# control.net
KiCad netlist of a schematic drawn in EAGLE
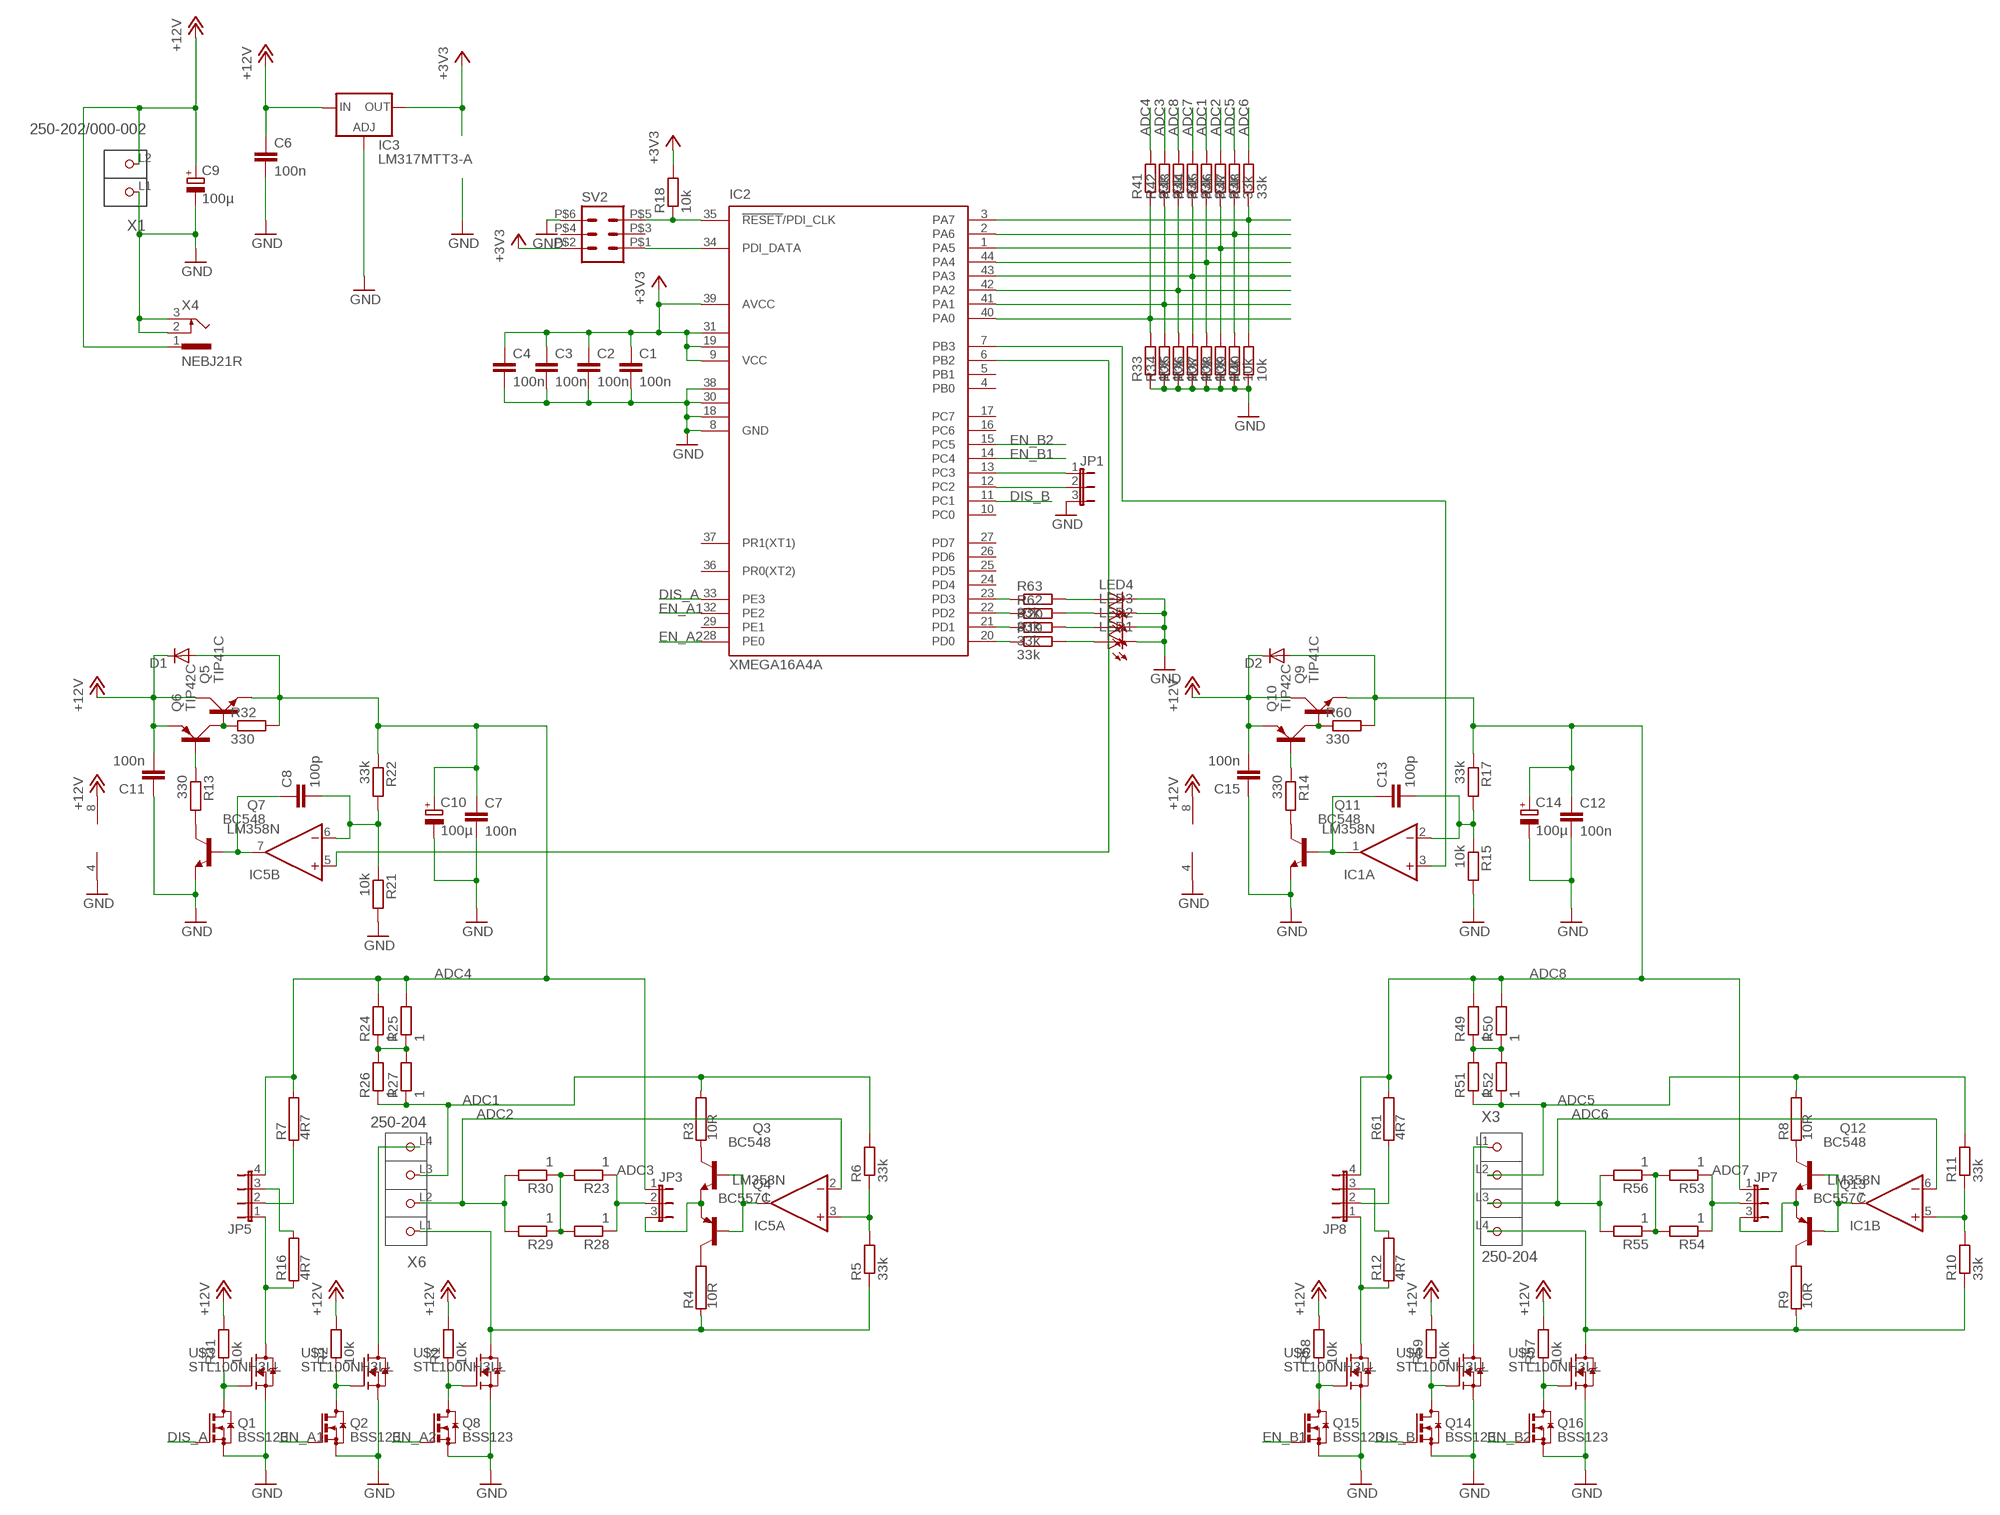
[diagram p0: schematic, sheet 1]

(export (version "E")
  (design (tool "Eeschema 10.0.6"))
  (components
    (comp (ref "C1")
      (value "100n")
      (footprint "eagle-import:C0805K")
      (libsource (lib "eagle-import") (part "C-EUC0805K"))
    )
    (comp (ref "C2")
      (value "100n")
      (footprint "eagle-import:C0805K")
      (libsource (lib "eagle-import") (part "C-EUC0805K"))
    )
    (comp (ref "C3")
      (value "100n")
      (footprint "eagle-import:C0805K")
      (libsource (lib "eagle-import") (part "C-EUC0805K"))
    )
    (comp (ref "C4")
      (value "100n")
      (footprint "eagle-import:C0805K")
      (libsource (lib "eagle-import") (part "C-EUC0805K"))
    )
    (comp (ref "C6")
      (value "100n")
      (footprint "eagle-import:C0805K")
      (libsource (lib "eagle-import") (part "C-EUC0805K"))
    )
    (comp (ref "C7")
      (value "100n")
      (footprint "eagle-import:C0805K")
      (libsource (lib "eagle-import") (part "C-EUC0805K"))
    )
    (comp (ref "C8")
      (value "100p")
      (footprint "eagle-import:C0805K")
      (libsource (lib "eagle-import") (part "C-EUC0805K"))
    )
    (comp (ref "C9")
      (value "100µ")
      (footprint "eagle-import:E2,5-7")
      (libsource (lib "eagle-import") (part "CPOL-EUE2.5-7"))
    )
    (comp (ref "C10")
      (value "100µ")
      (footprint "eagle-import:E2,5-7")
      (libsource (lib "eagle-import") (part "CPOL-EUE2.5-7"))
    )
    (comp (ref "C11")
      (value "100n")
      (footprint "eagle-import:C0805")
      (libsource (lib "eagle-import") (part "C-EUC0805"))
    )
    (comp (ref "C12")
      (value "100n")
      (footprint "eagle-import:C0805K")
      (libsource (lib "eagle-import") (part "C-EUC0805K"))
    )
    (comp (ref "C13")
      (value "100p")
      (footprint "eagle-import:C0805K")
      (libsource (lib "eagle-import") (part "C-EUC0805K"))
    )
    (comp (ref "C14")
      (value "100µ")
      (footprint "eagle-import:E2,5-7")
      (libsource (lib "eagle-import") (part "CPOL-EUE2.5-7"))
    )
    (comp (ref "C15")
      (value "100n")
      (footprint "eagle-import:C0805")
      (libsource (lib "eagle-import") (part "C-EUC0805"))
    )
    (comp (ref "D1")
      (value "DIODE-DO41-7.6")
      (footprint "eagle-import:DO41-7.6")
      (libsource (lib "eagle-import") (part "DIODE-DO41-7.6"))
    )
    (comp (ref "D2")
      (value "DIODE-DO41-7.6")
      (footprint "eagle-import:DO41-7.6")
      (libsource (lib "eagle-import") (part "DIODE-DO41-7.6"))
    )
    (comp (ref "IC1")
      (value "LM358N")
      (footprint "eagle-import:DIL08")
      (libsource (lib "eagle-import") (part "LM358N"))
    )
    (comp (ref "IC2")
      (value "XMEGA16A4A")
      (footprint "eagle-import:TQFP44")
      (libsource (lib "eagle-import") (part "XMEGA16A4A"))
    )
    (comp (ref "IC3")
      (value "LM317MTT3-A")
      (footprint "eagle-import:SOT223")
      (libsource (lib "eagle-import") (part "LM317?MTT3-A"))
    )
    (comp (ref "IC5")
      (value "LM358N")
      (footprint "eagle-import:DIL08")
      (libsource (lib "eagle-import") (part "LM358N"))
    )
    (comp (ref "JP1")
      (value "JP2E")
      (footprint "eagle-import:JP2")
      (libsource (lib "eagle-import") (part "JP2E"))
    )
    (comp (ref "JP3")
      (value "JP2E")
      (footprint "eagle-import:JP2")
      (libsource (lib "eagle-import") (part "JP2E"))
    )
    (comp (ref "JP5")
      (value "JP4E")
      (footprint "eagle-import:JP4")
      (libsource (lib "eagle-import") (part "JP4E"))
    )
    (comp (ref "JP7")
      (value "JP2E")
      (footprint "eagle-import:JP2")
      (libsource (lib "eagle-import") (part "JP2E"))
    )
    (comp (ref "JP8")
      (value "JP4E")
      (footprint "eagle-import:JP4")
      (libsource (lib "eagle-import") (part "JP4E"))
    )
    (comp (ref "LED1")
      (value "LEDCHIPLED_0805")
      (footprint "eagle-import:CHIPLED_0805")
      (libsource (lib "eagle-import") (part "LEDCHIPLED_0805"))
    )
    (comp (ref "LED2")
      (value "LEDCHIPLED_0805")
      (footprint "eagle-import:CHIPLED_0805")
      (libsource (lib "eagle-import") (part "LEDCHIPLED_0805"))
    )
    (comp (ref "LED3")
      (value "LEDCHIPLED_0805")
      (footprint "eagle-import:CHIPLED_0805")
      (libsource (lib "eagle-import") (part "LEDCHIPLED_0805"))
    )
    (comp (ref "LED4")
      (value "LEDCHIPLED_0805")
      (footprint "eagle-import:CHIPLED_0805")
      (libsource (lib "eagle-import") (part "LEDCHIPLED_0805"))
    )
    (comp (ref "Q1")
      (value "BSS123")
      (footprint "eagle-import:SOT23")
      (libsource (lib "eagle-import") (part "BSS123"))
    )
    (comp (ref "Q2")
      (value "BSS123")
      (footprint "eagle-import:SOT23")
      (libsource (lib "eagle-import") (part "BSS123"))
    )
    (comp (ref "Q3")
      (value "BC548")
      (footprint "eagle-import:TO92-EBC")
      (libsource (lib "eagle-import") (part "BC548"))
    )
    (comp (ref "Q4")
      (value "BC557C")
      (footprint "eagle-import:TO92-EBC")
      (libsource (lib "eagle-import") (part "BC557C"))
    )
    (comp (ref "Q5")
      (value "TIP41C")
      (footprint "eagle-import:TO220AV")
      (libsource (lib "eagle-import") (part "TIP41C"))
    )
    (comp (ref "Q6")
      (value "TIP42C")
      (footprint "eagle-import:TO220AV")
      (libsource (lib "eagle-import") (part "TIP42C"))
    )
    (comp (ref "Q7")
      (value "BC548")
      (footprint "eagle-import:TO92-EBC")
      (libsource (lib "eagle-import") (part "BC548"))
    )
    (comp (ref "Q8")
      (value "BSS123")
      (footprint "eagle-import:SOT23")
      (libsource (lib "eagle-import") (part "BSS123"))
    )
    (comp (ref "Q9")
      (value "TIP41C")
      (footprint "eagle-import:TO220AV")
      (libsource (lib "eagle-import") (part "TIP41C"))
    )
    (comp (ref "Q10")
      (value "TIP42C")
      (footprint "eagle-import:TO220AV")
      (libsource (lib "eagle-import") (part "TIP42C"))
    )
    (comp (ref "Q11")
      (value "BC548")
      (footprint "eagle-import:TO92-EBC")
      (libsource (lib "eagle-import") (part "BC548"))
    )
    (comp (ref "Q12")
      (value "BC548")
      (footprint "eagle-import:TO92-EBC")
      (libsource (lib "eagle-import") (part "BC548"))
    )
    (comp (ref "Q13")
      (value "BC557C")
      (footprint "eagle-import:TO92-EBC")
      (libsource (lib "eagle-import") (part "BC557C"))
    )
    (comp (ref "Q14")
      (value "BSS123")
      (footprint "eagle-import:SOT23")
      (libsource (lib "eagle-import") (part "BSS123"))
    )
    (comp (ref "Q15")
      (value "BSS123")
      (footprint "eagle-import:SOT23")
      (libsource (lib "eagle-import") (part "BSS123"))
    )
    (comp (ref "Q16")
      (value "BSS123")
      (footprint "eagle-import:SOT23")
      (libsource (lib "eagle-import") (part "BSS123"))
    )
    (comp (ref "R1")
      (value "10k")
      (footprint "eagle-import:M0805")
      (libsource (lib "eagle-import") (part "R-EU_M0805"))
    )
    (comp (ref "R2")
      (value "10k")
      (footprint "eagle-import:M0805")
      (libsource (lib "eagle-import") (part "R-EU_M0805"))
    )
    (comp (ref "R3")
      (value "10R")
      (footprint "eagle-import:HPS58")
      (libsource (lib "eagle-import") (part "RHPS58"))
    )
    (comp (ref "R4")
      (value "10R")
      (footprint "eagle-import:HPS58")
      (libsource (lib "eagle-import") (part "RHPS58"))
    )
    (comp (ref "R5")
      (value "33k")
      (footprint "eagle-import:M0805")
      (libsource (lib "eagle-import") (part "R-EU_M0805"))
    )
    (comp (ref "R6")
      (value "33k")
      (footprint "eagle-import:M0805")
      (libsource (lib "eagle-import") (part "R-EU_M0805"))
    )
    (comp (ref "R7")
      (value "4R7")
      (footprint "eagle-import:KH208R-8")
      (libsource (lib "eagle-import") (part "RKH208-8R"))
    )
    (comp (ref "R8")
      (value "10R")
      (footprint "eagle-import:HPS58")
      (libsource (lib "eagle-import") (part "RHPS58"))
    )
    (comp (ref "R9")
      (value "10R")
      (footprint "eagle-import:HPS58")
      (libsource (lib "eagle-import") (part "RHPS58"))
    )
    (comp (ref "R10")
      (value "33k")
      (footprint "eagle-import:M0805")
      (libsource (lib "eagle-import") (part "R-EU_M0805"))
    )
    (comp (ref "R11")
      (value "33k")
      (footprint "eagle-import:M0805")
      (libsource (lib "eagle-import") (part "R-EU_M0805"))
    )
    (comp (ref "R12")
      (value "4R7")
      (footprint "eagle-import:KH208R-8")
      (libsource (lib "eagle-import") (part "RKH208-8R"))
    )
    (comp (ref "R13")
      (value "330")
      (footprint "eagle-import:M0805")
      (libsource (lib "eagle-import") (part "R-EU_M0805"))
    )
    (comp (ref "R14")
      (value "330")
      (footprint "eagle-import:M0805")
      (libsource (lib "eagle-import") (part "R-EU_M0805"))
    )
    (comp (ref "R15")
      (value "10k")
      (footprint "eagle-import:M0805")
      (libsource (lib "eagle-import") (part "R-EU_M0805"))
    )
    (comp (ref "R16")
      (value "4R7")
      (footprint "eagle-import:KH208R-8")
      (libsource (lib "eagle-import") (part "RKH208-8R"))
    )
    (comp (ref "R17")
      (value "33k")
      (footprint "eagle-import:M0805")
      (libsource (lib "eagle-import") (part "R-EU_M0805"))
    )
    (comp (ref "R18")
      (value "10k")
      (footprint "eagle-import:M0805")
      (libsource (lib "eagle-import") (part "R-EU_M0805"))
    )
    (comp (ref "R19")
      (value "33k")
      (footprint "eagle-import:M0805")
      (libsource (lib "eagle-import") (part "R-EU_M0805"))
    )
    (comp (ref "R20")
      (value "33k")
      (footprint "eagle-import:M0805")
      (libsource (lib "eagle-import") (part "R-EU_M0805"))
    )
    (comp (ref "R21")
      (value "10k")
      (footprint "eagle-import:M0805")
      (libsource (lib "eagle-import") (part "R-EU_M0805"))
    )
    (comp (ref "R22")
      (value "33k")
      (footprint "eagle-import:M0805")
      (libsource (lib "eagle-import") (part "R-EU_M0805"))
    )
    (comp (ref "R23")
      (value "1")
      (footprint "eagle-import:0207_2V")
      (libsource (lib "eagle-import") (part "R-EU_0207/2V"))
    )
    (comp (ref "R24")
      (value "1")
      (footprint "eagle-import:0207_2V")
      (libsource (lib "eagle-import") (part "R-EU_0207/2V"))
    )
    (comp (ref "R25")
      (value "1")
      (footprint "eagle-import:0207_2V")
      (libsource (lib "eagle-import") (part "R-EU_0207/2V"))
    )
    (comp (ref "R26")
      (value "1")
      (footprint "eagle-import:0207_2V")
      (libsource (lib "eagle-import") (part "R-EU_0207/2V"))
    )
    (comp (ref "R27")
      (value "1")
      (footprint "eagle-import:0207_2V")
      (libsource (lib "eagle-import") (part "R-EU_0207/2V"))
    )
    (comp (ref "R28")
      (value "1")
      (footprint "eagle-import:0207_2V")
      (libsource (lib "eagle-import") (part "R-EU_0207/2V"))
    )
    (comp (ref "R29")
      (value "1")
      (footprint "eagle-import:0207_2V")
      (libsource (lib "eagle-import") (part "R-EU_0207/2V"))
    )
    (comp (ref "R30")
      (value "1")
      (footprint "eagle-import:0207_2V")
      (libsource (lib "eagle-import") (part "R-EU_0207/2V"))
    )
    (comp (ref "R31")
      (value "10k")
      (footprint "eagle-import:M0805")
      (libsource (lib "eagle-import") (part "R-EU_M0805"))
    )
    (comp (ref "R32")
      (value "330")
      (footprint "eagle-import:M0805")
      (libsource (lib "eagle-import") (part "R-EU_M0805"))
    )
    (comp (ref "R33")
      (value "10k")
      (footprint "eagle-import:M0805")
      (libsource (lib "eagle-import") (part "R-EU_M0805"))
    )
    (comp (ref "R34")
      (value "10k")
      (footprint "eagle-import:M0805")
      (libsource (lib "eagle-import") (part "R-EU_M0805"))
    )
    (comp (ref "R35")
      (value "10k")
      (footprint "eagle-import:M0805")
      (libsource (lib "eagle-import") (part "R-EU_M0805"))
    )
    (comp (ref "R36")
      (value "10k")
      (footprint "eagle-import:M0805")
      (libsource (lib "eagle-import") (part "R-EU_M0805"))
    )
    (comp (ref "R37")
      (value "10k")
      (footprint "eagle-import:M0805")
      (libsource (lib "eagle-import") (part "R-EU_M0805"))
    )
    (comp (ref "R38")
      (value "10k")
      (footprint "eagle-import:M0805")
      (libsource (lib "eagle-import") (part "R-EU_M0805"))
    )
    (comp (ref "R39")
      (value "10k")
      (footprint "eagle-import:M0805")
      (libsource (lib "eagle-import") (part "R-EU_M0805"))
    )
    (comp (ref "R40")
      (value "10k")
      (footprint "eagle-import:M0805")
      (libsource (lib "eagle-import") (part "R-EU_M0805"))
    )
    (comp (ref "R41")
      (value "33k")
      (footprint "eagle-import:M0805")
      (libsource (lib "eagle-import") (part "R-EU_M0805"))
    )
    (comp (ref "R42")
      (value "33k")
      (footprint "eagle-import:M0805")
      (libsource (lib "eagle-import") (part "R-EU_M0805"))
    )
    (comp (ref "R43")
      (value "33k")
      (footprint "eagle-import:M0805")
      (libsource (lib "eagle-import") (part "R-EU_M0805"))
    )
    (comp (ref "R44")
      (value "33k")
      (footprint "eagle-import:M0805")
      (libsource (lib "eagle-import") (part "R-EU_M0805"))
    )
    (comp (ref "R45")
      (value "33k")
      (footprint "eagle-import:M0805")
      (libsource (lib "eagle-import") (part "R-EU_M0805"))
    )
    (comp (ref "R46")
      (value "33k")
      (footprint "eagle-import:M0805")
      (libsource (lib "eagle-import") (part "R-EU_M0805"))
    )
    (comp (ref "R47")
      (value "33k")
      (footprint "eagle-import:M0805")
      (libsource (lib "eagle-import") (part "R-EU_M0805"))
    )
    (comp (ref "R48")
      (value "33k")
      (footprint "eagle-import:M0805")
      (libsource (lib "eagle-import") (part "R-EU_M0805"))
    )
    (comp (ref "R49")
      (value "1")
      (footprint "eagle-import:0207_2V")
      (libsource (lib "eagle-import") (part "R-EU_0207/2V"))
    )
    (comp (ref "R50")
      (value "1")
      (footprint "eagle-import:0207_2V")
      (libsource (lib "eagle-import") (part "R-EU_0207/2V"))
    )
    (comp (ref "R51")
      (value "1")
      (footprint "eagle-import:0207_2V")
      (libsource (lib "eagle-import") (part "R-EU_0207/2V"))
    )
    (comp (ref "R52")
      (value "1")
      (footprint "eagle-import:0207_2V")
      (libsource (lib "eagle-import") (part "R-EU_0207/2V"))
    )
    (comp (ref "R53")
      (value "1")
      (footprint "eagle-import:0207_2V")
      (libsource (lib "eagle-import") (part "R-EU_0207/2V"))
    )
    (comp (ref "R54")
      (value "1")
      (footprint "eagle-import:0207_2V")
      (libsource (lib "eagle-import") (part "R-EU_0207/2V"))
    )
    (comp (ref "R55")
      (value "1")
      (footprint "eagle-import:0207_2V")
      (libsource (lib "eagle-import") (part "R-EU_0207/2V"))
    )
    (comp (ref "R56")
      (value "1")
      (footprint "eagle-import:0207_2V")
      (libsource (lib "eagle-import") (part "R-EU_0207/2V"))
    )
    (comp (ref "R57")
      (value "10k")
      (footprint "eagle-import:M0805")
      (libsource (lib "eagle-import") (part "R-EU_M0805"))
    )
    (comp (ref "R58")
      (value "10k")
      (footprint "eagle-import:M0805")
      (libsource (lib "eagle-import") (part "R-EU_M0805"))
    )
    (comp (ref "R59")
      (value "10k")
      (footprint "eagle-import:M0805")
      (libsource (lib "eagle-import") (part "R-EU_M0805"))
    )
    (comp (ref "R60")
      (value "330")
      (footprint "eagle-import:M0805")
      (libsource (lib "eagle-import") (part "R-EU_M0805"))
    )
    (comp (ref "R61")
      (value "4R7")
      (footprint "eagle-import:KH208R-8")
      (libsource (lib "eagle-import") (part "RKH208-8R"))
    )
    (comp (ref "R62")
      (value "33k")
      (footprint "eagle-import:M0805")
      (libsource (lib "eagle-import") (part "R-EU_M0805"))
    )
    (comp (ref "R63")
      (value "33k")
      (footprint "eagle-import:M0805")
      (libsource (lib "eagle-import") (part "R-EU_M0805"))
    )
    (comp (ref "SV2")
      (value "ML66S")
      (footprint "eagle-import:ML6S")
      (libsource (lib "eagle-import") (part "ML66S"))
    )
    (comp (ref "U$1")
      (value "STL100NH3LL")
      (footprint "eagle-import:PG-TDSON-8")
      (libsource (lib "eagle-import") (part "STL100NH3LL"))
    )
    (comp (ref "U$2")
      (value "STL100NH3LL")
      (footprint "eagle-import:PG-TDSON-8")
      (libsource (lib "eagle-import") (part "STL100NH3LL"))
    )
    (comp (ref "U$3")
      (value "STL100NH3LL")
      (footprint "eagle-import:PG-TDSON-8")
      (libsource (lib "eagle-import") (part "STL100NH3LL"))
    )
    (comp (ref "U$4")
      (value "STL100NH3LL")
      (footprint "eagle-import:PG-TDSON-8")
      (libsource (lib "eagle-import") (part "STL100NH3LL"))
    )
    (comp (ref "U$5")
      (value "STL100NH3LL")
      (footprint "eagle-import:PG-TDSON-8")
      (libsource (lib "eagle-import") (part "STL100NH3LL"))
    )
    (comp (ref "U$6")
      (value "STL100NH3LL")
      (footprint "eagle-import:PG-TDSON-8")
      (libsource (lib "eagle-import") (part "STL100NH3LL"))
    )
    (comp (ref "X1")
      (value "250-202/000-002")
      (footprint "eagle-import:P-250-202")
      (libsource (lib "eagle-import") (part "250-202/000-002"))
    )
    (comp (ref "X3")
      (value "250-204")
      (footprint "eagle-import:P-250-204")
      (libsource (lib "eagle-import") (part "250-204"))
    )
    (comp (ref "X4")
      (value "NEBJ21R")
      (footprint "eagle-import:NEBJ21R")
      (fields (field (name "MPN") "NEB/J 21 R"))
      (libsource (lib "eagle-import") (part "NEBJ21R"))
    )
    (comp (ref "X6")
      (value "250-204")
      (footprint "eagle-import:P-250-204")
      (libsource (lib "eagle-import") (part "250-204"))
    )
  )
  (nets
    (net (code "1") (name "+3V3") (class "Default")
      (node (ref "C1") (pin "1") (pinfunction "1_1") (pintype "passive"))
      (node (ref "C2") (pin "1") (pinfunction "1_1") (pintype "passive"))
      (node (ref "C3") (pin "1") (pinfunction "1_1") (pintype "passive"))
      (node (ref "C4") (pin "1") (pinfunction "1_1") (pintype "passive"))
      (node (ref "IC2") (pin "19") (pinfunction "VCC1_19") (pintype "power_in"))
      (node (ref "IC2") (pin "31") (pinfunction "VCC2_31") (pintype "power_in"))
      (node (ref "IC2") (pin "39") (pinfunction "AVCC_39") (pintype "power_in"))
      (node (ref "IC2") (pin "9") (pinfunction "VCC_9") (pintype "power_in"))
      (node (ref "IC3") (pin "2") (pinfunction "OUT_2") (pintype "passive"))
      (node (ref "R18") (pin "2") (pinfunction "2_2") (pintype "passive"))
      (node (ref "SV2") (pin "P$2") (pinfunction "2_P$2") (pintype "passive"))
    )
    (net (code "2") (name "+12V") (class "Default")
      (node (ref "C11") (pin "2") (pinfunction "2_2") (pintype "passive"))
      (node (ref "C15") (pin "2") (pinfunction "2_2") (pintype "passive"))
      (node (ref "C6") (pin "1") (pinfunction "1_1") (pintype "passive"))
      (node (ref "C9") (pin "+") (pinfunction "+_+") (pintype "passive"))
      (node (ref "D1") (pin "C") (pinfunction "C_C") (pintype "passive"))
      (node (ref "D2") (pin "C") (pinfunction "C_C") (pintype "passive"))
      (node (ref "IC1") (pin "8") (pinfunction "V+_8") (pintype "power_in"))
      (node (ref "IC3") (pin "3") (pinfunction "IN_3") (pintype "input"))
      (node (ref "IC5") (pin "8") (pinfunction "V+_8") (pintype "power_in"))
      (node (ref "Q10") (pin "E") (pinfunction "E_E") (pintype "passive"))
      (node (ref "Q5") (pin "C") (pinfunction "C_C") (pintype "passive"))
      (node (ref "Q6") (pin "E") (pinfunction "E_E") (pintype "passive"))
      (node (ref "Q9") (pin "C") (pinfunction "C_C") (pintype "passive"))
      (node (ref "R1") (pin "2") (pinfunction "2_2") (pintype "passive"))
      (node (ref "R2") (pin "2") (pinfunction "2_2") (pintype "passive"))
      (node (ref "R31") (pin "2") (pinfunction "2_2") (pintype "passive"))
      (node (ref "R57") (pin "2") (pinfunction "2_2") (pintype "passive"))
      (node (ref "R58") (pin "2") (pinfunction "2_2") (pintype "passive"))
      (node (ref "R59") (pin "2") (pinfunction "2_2") (pintype "passive"))
      (node (ref "X1") (pin "L2") (pinfunction "P2_L2") (pintype "bidirectional"))
      (node (ref "X4") (pin "1") (pinfunction "1_1") (pintype "passive"))
    )
    (net (code "3") (name "/ADC1") (class "Default")
      (node (ref "R26") (pin "1") (pinfunction "1_1") (pintype "passive"))
      (node (ref "R27") (pin "1") (pinfunction "1_1") (pintype "passive"))
      (node (ref "R3") (pin "2") (pinfunction "2_2") (pintype "passive"))
      (node (ref "R45") (pin "2") (pinfunction "2_2") (pintype "passive"))
      (node (ref "R6") (pin "2") (pinfunction "2_2") (pintype "passive"))
      (node (ref "X6") (pin "L3") (pinfunction "P3_L3") (pintype "bidirectional"))
    )
    (net (code "4") (name "/ADC2") (class "Default")
      (node (ref "IC5") (pin "2") (pinfunction "-IN_2") (pintype "input"))
      (node (ref "R29") (pin "2") (pinfunction "2_2") (pintype "passive"))
      (node (ref "R30") (pin "2") (pinfunction "2_2") (pintype "passive"))
      (node (ref "R46") (pin "2") (pinfunction "2_2") (pintype "passive"))
      (node (ref "X6") (pin "L2") (pinfunction "P2_L2") (pintype "bidirectional"))
    )
    (net (code "5") (name "/ADC3") (class "Default")
      (node (ref "JP3") (pin "2") (pinfunction "2_2") (pintype "passive"))
      (node (ref "R23") (pin "1") (pinfunction "1_1") (pintype "passive"))
      (node (ref "R28") (pin "1") (pinfunction "1_1") (pintype "passive"))
      (node (ref "R42") (pin "2") (pinfunction "2_2") (pintype "passive"))
    )
    (net (code "6") (name "/ADC4") (class "Default")
      (node (ref "C10") (pin "+") (pinfunction "+_+") (pintype "passive"))
      (node (ref "C7") (pin "1") (pinfunction "1_1") (pintype "passive"))
      (node (ref "D1") (pin "A") (pinfunction "A_A") (pintype "passive"))
      (node (ref "JP3") (pin "1") (pinfunction "1_1") (pintype "passive"))
      (node (ref "JP5") (pin "4") (pinfunction "4_4") (pintype "passive"))
      (node (ref "Q5") (pin "E") (pinfunction "E_E") (pintype "passive"))
      (node (ref "R22") (pin "1") (pinfunction "1_1") (pintype "passive"))
      (node (ref "R24") (pin "2") (pinfunction "2_2") (pintype "passive"))
      (node (ref "R25") (pin "2") (pinfunction "2_2") (pintype "passive"))
      (node (ref "R32") (pin "2") (pinfunction "2_2") (pintype "passive"))
      (node (ref "R41") (pin "2") (pinfunction "2_2") (pintype "passive"))
      (node (ref "R7") (pin "2") (pinfunction "2_2") (pintype "passive"))
    )
    (net (code "7") (name "/ADC5") (class "Default")
      (node (ref "R11") (pin "2") (pinfunction "2_2") (pintype "passive"))
      (node (ref "R47") (pin "2") (pinfunction "2_2") (pintype "passive"))
      (node (ref "R51") (pin "1") (pinfunction "1_1") (pintype "passive"))
      (node (ref "R52") (pin "1") (pinfunction "1_1") (pintype "passive"))
      (node (ref "R8") (pin "2") (pinfunction "2_2") (pintype "passive"))
      (node (ref "X3") (pin "L2") (pinfunction "P2_L2") (pintype "bidirectional"))
    )
    (net (code "8") (name "/ADC6") (class "Default")
      (node (ref "IC1") (pin "6") (pinfunction "-IN_6") (pintype "input"))
      (node (ref "R48") (pin "2") (pinfunction "2_2") (pintype "passive"))
      (node (ref "R55") (pin "2") (pinfunction "2_2") (pintype "passive"))
      (node (ref "R56") (pin "2") (pinfunction "2_2") (pintype "passive"))
      (node (ref "X3") (pin "L3") (pinfunction "P3_L3") (pintype "bidirectional"))
    )
    (net (code "9") (name "/ADC7") (class "Default")
      (node (ref "JP7") (pin "2") (pinfunction "2_2") (pintype "passive"))
      (node (ref "R44") (pin "2") (pinfunction "2_2") (pintype "passive"))
      (node (ref "R53") (pin "1") (pinfunction "1_1") (pintype "passive"))
      (node (ref "R54") (pin "1") (pinfunction "1_1") (pintype "passive"))
    )
    (net (code "10") (name "/ADC8") (class "Default")
      (node (ref "C12") (pin "1") (pinfunction "1_1") (pintype "passive"))
      (node (ref "C14") (pin "+") (pinfunction "+_+") (pintype "passive"))
      (node (ref "D2") (pin "A") (pinfunction "A_A") (pintype "passive"))
      (node (ref "JP7") (pin "1") (pinfunction "1_1") (pintype "passive"))
      (node (ref "JP8") (pin "4") (pinfunction "4_4") (pintype "passive"))
      (node (ref "Q9") (pin "E") (pinfunction "E_E") (pintype "passive"))
      (node (ref "R17") (pin "1") (pinfunction "1_1") (pintype "passive"))
      (node (ref "R43") (pin "2") (pinfunction "2_2") (pintype "passive"))
      (node (ref "R49") (pin "2") (pinfunction "2_2") (pintype "passive"))
      (node (ref "R50") (pin "2") (pinfunction "2_2") (pintype "passive"))
      (node (ref "R60") (pin "2") (pinfunction "2_2") (pintype "passive"))
      (node (ref "R61") (pin "2") (pinfunction "2_2") (pintype "passive"))
    )
    (net (code "11") (name "/DIS_A") (class "Default")
      (node (ref "IC2") (pin "33") (pinfunction "PE3_33") (pintype "bidirectional"))
      (node (ref "Q1") (pin "1") (pinfunction "G_1") (pintype "passive"))
    )
    (net (code "12") (name "/DIS_B") (class "Default")
      (node (ref "IC2") (pin "11") (pinfunction "PC1_11") (pintype "bidirectional"))
      (node (ref "Q14") (pin "1") (pinfunction "G_1") (pintype "passive"))
    )
    (net (code "13") (name "/EN_A1") (class "Default")
      (node (ref "IC2") (pin "32") (pinfunction "PE2_32") (pintype "bidirectional"))
      (node (ref "Q2") (pin "1") (pinfunction "G_1") (pintype "passive"))
    )
    (net (code "14") (name "/EN_A2") (class "Default")
      (node (ref "IC2") (pin "28") (pinfunction "PE0_28") (pintype "bidirectional"))
      (node (ref "Q8") (pin "1") (pinfunction "G_1") (pintype "passive"))
    )
    (net (code "15") (name "/EN_B1") (class "Default")
      (node (ref "IC2") (pin "14") (pinfunction "PC4_14") (pintype "bidirectional"))
      (node (ref "Q15") (pin "1") (pinfunction "G_1") (pintype "passive"))
    )
    (net (code "16") (name "/EN_B2") (class "Default")
      (node (ref "IC2") (pin "15") (pinfunction "PC5_15") (pintype "bidirectional"))
      (node (ref "Q16") (pin "1") (pinfunction "G_1") (pintype "passive"))
    )
    (net (code "17") (name "GND") (class "Default")
      (node (ref "C1") (pin "2") (pinfunction "2_2") (pintype "passive"))
      (node (ref "C10") (pin "-") (pinfunction "-_-") (pintype "passive"))
      (node (ref "C11") (pin "1") (pinfunction "1_1") (pintype "passive"))
      (node (ref "C12") (pin "2") (pinfunction "2_2") (pintype "passive"))
      (node (ref "C14") (pin "-") (pinfunction "-_-") (pintype "passive"))
      (node (ref "C15") (pin "1") (pinfunction "1_1") (pintype "passive"))
      (node (ref "C2") (pin "2") (pinfunction "2_2") (pintype "passive"))
      (node (ref "C3") (pin "2") (pinfunction "2_2") (pintype "passive"))
      (node (ref "C4") (pin "2") (pinfunction "2_2") (pintype "passive"))
      (node (ref "C6") (pin "2") (pinfunction "2_2") (pintype "passive"))
      (node (ref "C7") (pin "2") (pinfunction "2_2") (pintype "passive"))
      (node (ref "C9") (pin "-") (pinfunction "-_-") (pintype "passive"))
      (node (ref "IC1") (pin "4") (pinfunction "V-_4") (pintype "power_in"))
      (node (ref "IC2") (pin "18") (pinfunction "GND1_18") (pintype "power_in"))
      (node (ref "IC2") (pin "30") (pinfunction "GND2_30") (pintype "power_in"))
      (node (ref "IC2") (pin "38") (pinfunction "GND3_38") (pintype "power_in"))
      (node (ref "IC2") (pin "8") (pinfunction "GND_8") (pintype "power_in"))
      (node (ref "IC3") (pin "1") (pinfunction "ADJ_1") (pintype "input"))
      (node (ref "IC5") (pin "4") (pinfunction "V-_4") (pintype "power_in"))
      (node (ref "JP1") (pin "3") (pinfunction "3_3") (pintype "passive"))
      (node (ref "LED1") (pin "C") (pinfunction "C_C") (pintype "passive"))
      (node (ref "LED2") (pin "C") (pinfunction "C_C") (pintype "passive"))
      (node (ref "LED3") (pin "C") (pinfunction "C_C") (pintype "passive"))
      (node (ref "LED4") (pin "C") (pinfunction "C_C") (pintype "passive"))
      (node (ref "Q1") (pin "2") (pinfunction "S_2") (pintype "passive"))
      (node (ref "Q11") (pin "E") (pinfunction "E_E") (pintype "passive"))
      (node (ref "Q14") (pin "2") (pinfunction "S_2") (pintype "passive"))
      (node (ref "Q15") (pin "2") (pinfunction "S_2") (pintype "passive"))
      (node (ref "Q16") (pin "2") (pinfunction "S_2") (pintype "passive"))
      (node (ref "Q2") (pin "2") (pinfunction "S_2") (pintype "passive"))
      (node (ref "Q7") (pin "E") (pinfunction "E_E") (pintype "passive"))
      (node (ref "Q8") (pin "2") (pinfunction "S_2") (pintype "passive"))
      (node (ref "R15") (pin "2") (pinfunction "2_2") (pintype "passive"))
      (node (ref "R21") (pin "2") (pinfunction "2_2") (pintype "passive"))
      (node (ref "R33") (pin "1") (pinfunction "1_1") (pintype "passive"))
      (node (ref "R34") (pin "1") (pinfunction "1_1") (pintype "passive"))
      (node (ref "R35") (pin "1") (pinfunction "1_1") (pintype "passive"))
      (node (ref "R36") (pin "1") (pinfunction "1_1") (pintype "passive"))
      (node (ref "R37") (pin "1") (pinfunction "1_1") (pintype "passive"))
      (node (ref "R38") (pin "1") (pinfunction "1_1") (pintype "passive"))
      (node (ref "R39") (pin "1") (pinfunction "1_1") (pintype "passive"))
      (node (ref "R40") (pin "1") (pinfunction "1_1") (pintype "passive"))
      (node (ref "SV2") (pin "P$6") (pinfunction "6_P$6") (pintype "passive"))
      (node (ref "U$1") (pin "1") (pinfunction "S_1") (pintype "passive"))
      (node (ref "U$1") (pin "2") (pinfunction "S_2") (pintype "passive"))
      (node (ref "U$1") (pin "3") (pinfunction "S_3") (pintype "passive"))
      (node (ref "U$2") (pin "1") (pinfunction "S_1") (pintype "passive"))
      (node (ref "U$2") (pin "2") (pinfunction "S_2") (pintype "passive"))
      (node (ref "U$2") (pin "3") (pinfunction "S_3") (pintype "passive"))
      (node (ref "U$3") (pin "1") (pinfunction "S_1") (pintype "passive"))
      (node (ref "U$3") (pin "2") (pinfunction "S_2") (pintype "passive"))
      (node (ref "U$3") (pin "3") (pinfunction "S_3") (pintype "passive"))
      (node (ref "U$4") (pin "1") (pinfunction "S_1") (pintype "passive"))
      (node (ref "U$4") (pin "2") (pinfunction "S_2") (pintype "passive"))
      (node (ref "U$4") (pin "3") (pinfunction "S_3") (pintype "passive"))
      (node (ref "U$5") (pin "1") (pinfunction "S_1") (pintype "passive"))
      (node (ref "U$5") (pin "2") (pinfunction "S_2") (pintype "passive"))
      (node (ref "U$5") (pin "3") (pinfunction "S_3") (pintype "passive"))
      (node (ref "U$6") (pin "1") (pinfunction "S_1") (pintype "passive"))
      (node (ref "U$6") (pin "2") (pinfunction "S_2") (pintype "passive"))
      (node (ref "U$6") (pin "3") (pinfunction "S_3") (pintype "passive"))
      (node (ref "X1") (pin "L1") (pinfunction "P1_L1") (pintype "bidirectional"))
      (node (ref "X4") (pin "2") (pinfunction "2_2") (pintype "passive"))
      (node (ref "X4") (pin "3") (pinfunction "3_3") (pintype "passive"))
    )
    (net (code "18") (name "Net-(IC1A-+IN)") (class "Default")
      (node (ref "IC1") (pin "3") (pinfunction "+IN_3") (pintype "input"))
      (node (ref "IC2") (pin "7") (pinfunction "PB3_7") (pintype "bidirectional"))
    )
    (net (code "19") (name "Net-(IC1A--IN)") (class "Default")
      (node (ref "C13") (pin "2") (pinfunction "2_2") (pintype "passive"))
      (node (ref "IC1") (pin "2") (pinfunction "-IN_2") (pintype "input"))
      (node (ref "R15") (pin "1") (pinfunction "1_1") (pintype "passive"))
      (node (ref "R17") (pin "2") (pinfunction "2_2") (pintype "passive"))
    )
    (net (code "20") (name "Net-(IC1A-OUT)") (class "Default")
      (node (ref "C13") (pin "1") (pinfunction "1_1") (pintype "passive"))
      (node (ref "IC1") (pin "1") (pinfunction "OUT_1") (pintype "output"))
      (node (ref "Q11") (pin "B") (pinfunction "B_B") (pintype "passive"))
    )
    (net (code "21") (name "Net-(IC1B-+IN)") (class "Default")
      (node (ref "IC1") (pin "5") (pinfunction "+IN_5") (pintype "input"))
      (node (ref "R10") (pin "2") (pinfunction "2_2") (pintype "passive"))
      (node (ref "R11") (pin "1") (pinfunction "1_1") (pintype "passive"))
    )
    (net (code "22") (name "Net-(IC1B-OUT)") (class "Default")
      (node (ref "IC1") (pin "7") (pinfunction "OUT_7") (pintype "output"))
      (node (ref "Q12") (pin "B") (pinfunction "B_B") (pintype "passive"))
      (node (ref "Q13") (pin "B") (pinfunction "B_B") (pintype "passive"))
    )
    (net (code "23") (name "Net-(IC2-PA0)") (class "Default")
      (node (ref "IC2") (pin "40") (pinfunction "PA0_40") (pintype "bidirectional"))
      (node (ref "R33") (pin "2") (pinfunction "2_2") (pintype "passive"))
      (node (ref "R41") (pin "1") (pinfunction "1_1") (pintype "passive"))
    )
    (net (code "24") (name "Net-(IC2-PA1)") (class "Default")
      (node (ref "IC2") (pin "41") (pinfunction "PA1_41") (pintype "bidirectional"))
      (node (ref "R34") (pin "2") (pinfunction "2_2") (pintype "passive"))
      (node (ref "R42") (pin "1") (pinfunction "1_1") (pintype "passive"))
    )
    (net (code "25") (name "Net-(IC2-PA2)") (class "Default")
      (node (ref "IC2") (pin "42") (pinfunction "PA2_42") (pintype "bidirectional"))
      (node (ref "R35") (pin "2") (pinfunction "2_2") (pintype "passive"))
      (node (ref "R43") (pin "1") (pinfunction "1_1") (pintype "passive"))
    )
    (net (code "26") (name "Net-(IC2-PA3)") (class "Default")
      (node (ref "IC2") (pin "43") (pinfunction "PA3_43") (pintype "bidirectional"))
      (node (ref "R36") (pin "2") (pinfunction "2_2") (pintype "passive"))
      (node (ref "R44") (pin "1") (pinfunction "1_1") (pintype "passive"))
    )
    (net (code "27") (name "Net-(IC2-PA4)") (class "Default")
      (node (ref "IC2") (pin "44") (pinfunction "PA4_44") (pintype "bidirectional"))
      (node (ref "R37") (pin "2") (pinfunction "2_2") (pintype "passive"))
      (node (ref "R45") (pin "1") (pinfunction "1_1") (pintype "passive"))
    )
    (net (code "28") (name "Net-(IC2-PA5)") (class "Default")
      (node (ref "IC2") (pin "1") (pinfunction "PA5_1") (pintype "bidirectional"))
      (node (ref "R38") (pin "2") (pinfunction "2_2") (pintype "passive"))
      (node (ref "R46") (pin "1") (pinfunction "1_1") (pintype "passive"))
    )
    (net (code "29") (name "Net-(IC2-PA6)") (class "Default")
      (node (ref "IC2") (pin "2") (pinfunction "PA6_2") (pintype "bidirectional"))
      (node (ref "R39") (pin "2") (pinfunction "2_2") (pintype "passive"))
      (node (ref "R47") (pin "1") (pinfunction "1_1") (pintype "passive"))
    )
    (net (code "30") (name "Net-(IC2-PA7)") (class "Default")
      (node (ref "IC2") (pin "3") (pinfunction "PA7_3") (pintype "bidirectional"))
      (node (ref "R40") (pin "2") (pinfunction "2_2") (pintype "passive"))
      (node (ref "R48") (pin "1") (pinfunction "1_1") (pintype "passive"))
    )
    (net (code "31") (name "Net-(IC2-PB2)") (class "Default")
      (node (ref "IC2") (pin "6") (pinfunction "PB2_6") (pintype "bidirectional"))
      (node (ref "IC5") (pin "5") (pinfunction "+IN_5") (pintype "input"))
    )
    (net (code "32") (name "Net-(IC2-PC2)") (class "Default")
      (node (ref "IC2") (pin "12") (pinfunction "PC2_12") (pintype "bidirectional"))
      (node (ref "JP1") (pin "2") (pinfunction "2_2") (pintype "passive"))
    )
    (net (code "33") (name "Net-(IC2-PC3)") (class "Default")
      (node (ref "IC2") (pin "13") (pinfunction "PC3_13") (pintype "bidirectional"))
      (node (ref "JP1") (pin "1") (pinfunction "1_1") (pintype "passive"))
    )
    (net (code "34") (name "Net-(IC2-PD0)") (class "Default")
      (node (ref "IC2") (pin "20") (pinfunction "PD0_20") (pintype "bidirectional"))
      (node (ref "R19") (pin "1") (pinfunction "1_1") (pintype "passive"))
    )
    (net (code "35") (name "Net-(IC2-PD1)") (class "Default")
      (node (ref "IC2") (pin "21") (pinfunction "PD1_21") (pintype "bidirectional"))
      (node (ref "R20") (pin "1") (pinfunction "1_1") (pintype "passive"))
    )
    (net (code "36") (name "Net-(IC2-PD2)") (class "Default")
      (node (ref "IC2") (pin "22") (pinfunction "PD2_22") (pintype "bidirectional"))
      (node (ref "R62") (pin "1") (pinfunction "1_1") (pintype "passive"))
    )
    (net (code "37") (name "Net-(IC2-PD3)") (class "Default")
      (node (ref "IC2") (pin "23") (pinfunction "PD3_23") (pintype "bidirectional"))
      (node (ref "R63") (pin "1") (pinfunction "1_1") (pintype "passive"))
    )
    (net (code "38") (name "Net-(IC2-PDI_DATA)") (class "Default")
      (node (ref "IC2") (pin "34") (pinfunction "PDI_DATA_34") (pintype "bidirectional"))
      (node (ref "SV2") (pin "P$1") (pinfunction "1_P$1") (pintype "passive"))
    )
    (net (code "39") (name "Net-(IC2-~{RESET}{slash}PDI_CLK)") (class "Default")
      (node (ref "IC2") (pin "35") (pinfunction "~{RESET}/PDI_CLK_35") (pintype "bidirectional"))
      (node (ref "R18") (pin "1") (pinfunction "1_1") (pintype "passive"))
      (node (ref "SV2") (pin "P$5") (pinfunction "5_P$5") (pintype "passive"))
    )
    (net (code "40") (name "Net-(IC5A-+IN)") (class "Default")
      (node (ref "IC5") (pin "3") (pinfunction "+IN_3") (pintype "input"))
      (node (ref "R5") (pin "2") (pinfunction "2_2") (pintype "passive"))
      (node (ref "R6") (pin "1") (pinfunction "1_1") (pintype "passive"))
    )
    (net (code "41") (name "Net-(IC5A-OUT)") (class "Default")
      (node (ref "IC5") (pin "1") (pinfunction "OUT_1") (pintype "output"))
      (node (ref "Q3") (pin "B") (pinfunction "B_B") (pintype "passive"))
      (node (ref "Q4") (pin "B") (pinfunction "B_B") (pintype "passive"))
    )
    (net (code "42") (name "Net-(IC5B--IN)") (class "Default")
      (node (ref "C8") (pin "2") (pinfunction "2_2") (pintype "passive"))
      (node (ref "IC5") (pin "6") (pinfunction "-IN_6") (pintype "input"))
      (node (ref "R21") (pin "1") (pinfunction "1_1") (pintype "passive"))
      (node (ref "R22") (pin "2") (pinfunction "2_2") (pintype "passive"))
    )
    (net (code "43") (name "Net-(IC5B-OUT)") (class "Default")
      (node (ref "C8") (pin "1") (pinfunction "1_1") (pintype "passive"))
      (node (ref "IC5") (pin "7") (pinfunction "OUT_7") (pintype "output"))
      (node (ref "Q7") (pin "B") (pinfunction "B_B") (pintype "passive"))
    )
    (net (code "44") (name "Net-(JP3-Pad3)") (class "Default")
      (node (ref "JP3") (pin "3") (pinfunction "3_3") (pintype "passive"))
      (node (ref "Q3") (pin "E") (pinfunction "E_E") (pintype "passive"))
      (node (ref "Q4") (pin "E") (pinfunction "E_E") (pintype "passive"))
    )
    (net (code "45") (name "Net-(JP5-Pad1)") (class "Default")
      (node (ref "JP5") (pin "1") (pinfunction "1_1") (pintype "passive"))
      (node (ref "R16") (pin "1") (pinfunction "1_1") (pintype "passive"))
      (node (ref "U$3") (pin "5") (pinfunction "D_5") (pintype "passive"))
      (node (ref "U$3") (pin "6") (pinfunction "D_6") (pintype "passive"))
      (node (ref "U$3") (pin "7") (pinfunction "D_7") (pintype "passive"))
      (node (ref "U$3") (pin "8") (pinfunction "D_8") (pintype "passive"))
      (node (ref "U$3") (pin "TH") (pinfunction "D_TH") (pintype "passive"))
    )
    (net (code "46") (name "Net-(JP5-Pad2)") (class "Default")
      (node (ref "JP5") (pin "2") (pinfunction "2_2") (pintype "passive"))
      (node (ref "R7") (pin "1") (pinfunction "1_1") (pintype "passive"))
    )
    (net (code "47") (name "Net-(JP5-Pad3)") (class "Default")
      (node (ref "JP5") (pin "3") (pinfunction "3_3") (pintype "passive"))
      (node (ref "R16") (pin "2") (pinfunction "2_2") (pintype "passive"))
    )
    (net (code "48") (name "Net-(JP7-Pad3)") (class "Default")
      (node (ref "JP7") (pin "3") (pinfunction "3_3") (pintype "passive"))
      (node (ref "Q12") (pin "E") (pinfunction "E_E") (pintype "passive"))
      (node (ref "Q13") (pin "E") (pinfunction "E_E") (pintype "passive"))
    )
    (net (code "49") (name "Net-(JP8-Pad1)") (class "Default")
      (node (ref "JP8") (pin "1") (pinfunction "1_1") (pintype "passive"))
      (node (ref "R12") (pin "1") (pinfunction "1_1") (pintype "passive"))
      (node (ref "U$6") (pin "5") (pinfunction "D_5") (pintype "passive"))
      (node (ref "U$6") (pin "6") (pinfunction "D_6") (pintype "passive"))
      (node (ref "U$6") (pin "7") (pinfunction "D_7") (pintype "passive"))
      (node (ref "U$6") (pin "8") (pinfunction "D_8") (pintype "passive"))
      (node (ref "U$6") (pin "TH") (pinfunction "D_TH") (pintype "passive"))
    )
    (net (code "50") (name "Net-(JP8-Pad2)") (class "Default")
      (node (ref "JP8") (pin "2") (pinfunction "2_2") (pintype "passive"))
      (node (ref "R61") (pin "1") (pinfunction "1_1") (pintype "passive"))
    )
    (net (code "51") (name "Net-(JP8-Pad3)") (class "Default")
      (node (ref "JP8") (pin "3") (pinfunction "3_3") (pintype "passive"))
      (node (ref "R12") (pin "2") (pinfunction "2_2") (pintype "passive"))
    )
    (net (code "52") (name "Net-(LED1-PadA)") (class "Default")
      (node (ref "LED1") (pin "A") (pinfunction "A_A") (pintype "passive"))
      (node (ref "R19") (pin "2") (pinfunction "2_2") (pintype "passive"))
    )
    (net (code "53") (name "Net-(LED2-PadA)") (class "Default")
      (node (ref "LED2") (pin "A") (pinfunction "A_A") (pintype "passive"))
      (node (ref "R20") (pin "2") (pinfunction "2_2") (pintype "passive"))
    )
    (net (code "54") (name "Net-(LED3-PadA)") (class "Default")
      (node (ref "LED3") (pin "A") (pinfunction "A_A") (pintype "passive"))
      (node (ref "R62") (pin "2") (pinfunction "2_2") (pintype "passive"))
    )
    (net (code "55") (name "Net-(LED4-PadA)") (class "Default")
      (node (ref "LED4") (pin "A") (pinfunction "A_A") (pintype "passive"))
      (node (ref "R63") (pin "2") (pinfunction "2_2") (pintype "passive"))
    )
    (net (code "56") (name "Net-(Q1-D)") (class "Default")
      (node (ref "Q1") (pin "3") (pinfunction "D_3") (pintype "passive"))
      (node (ref "R31") (pin "1") (pinfunction "1_1") (pintype "passive"))
      (node (ref "U$3") (pin "4") (pinfunction "G_4") (pintype "passive"))
    )
    (net (code "57") (name "Net-(Q2-D)") (class "Default")
      (node (ref "Q2") (pin "3") (pinfunction "D_3") (pintype "passive"))
      (node (ref "R2") (pin "1") (pinfunction "1_1") (pintype "passive"))
      (node (ref "U$1") (pin "4") (pinfunction "G_4") (pintype "passive"))
    )
    (net (code "58") (name "Net-(Q3-PadC)") (class "Default")
      (node (ref "Q3") (pin "C") (pinfunction "C_C") (pintype "passive"))
      (node (ref "R3") (pin "1") (pinfunction "1_1") (pintype "passive"))
    )
    (net (code "59") (name "Net-(Q4-PadC)") (class "Default")
      (node (ref "Q4") (pin "C") (pinfunction "C_C") (pintype "passive"))
      (node (ref "R4") (pin "2") (pinfunction "2_2") (pintype "passive"))
    )
    (net (code "60") (name "Net-(Q5-PadB)") (class "Default")
      (node (ref "Q5") (pin "B") (pinfunction "B_B") (pintype "passive"))
      (node (ref "Q6") (pin "C") (pinfunction "C_C") (pintype "passive"))
      (node (ref "R32") (pin "1") (pinfunction "1_1") (pintype "passive"))
    )
    (net (code "61") (name "Net-(Q6-PadB)") (class "Default")
      (node (ref "Q6") (pin "B") (pinfunction "B_B") (pintype "passive"))
      (node (ref "R13") (pin "1") (pinfunction "1_1") (pintype "passive"))
    )
    (net (code "62") (name "Net-(Q7-PadC)") (class "Default")
      (node (ref "Q7") (pin "C") (pinfunction "C_C") (pintype "passive"))
      (node (ref "R13") (pin "2") (pinfunction "2_2") (pintype "passive"))
    )
    (net (code "63") (name "Net-(Q8-D)") (class "Default")
      (node (ref "Q8") (pin "3") (pinfunction "D_3") (pintype "passive"))
      (node (ref "R1") (pin "1") (pinfunction "1_1") (pintype "passive"))
      (node (ref "U$2") (pin "4") (pinfunction "G_4") (pintype "passive"))
    )
    (net (code "64") (name "Net-(Q10-PadB)") (class "Default")
      (node (ref "Q10") (pin "B") (pinfunction "B_B") (pintype "passive"))
      (node (ref "R14") (pin "1") (pinfunction "1_1") (pintype "passive"))
    )
    (net (code "65") (name "Net-(Q10-PadC)") (class "Default")
      (node (ref "Q10") (pin "C") (pinfunction "C_C") (pintype "passive"))
      (node (ref "Q9") (pin "B") (pinfunction "B_B") (pintype "passive"))
      (node (ref "R60") (pin "1") (pinfunction "1_1") (pintype "passive"))
    )
    (net (code "66") (name "Net-(Q11-PadC)") (class "Default")
      (node (ref "Q11") (pin "C") (pinfunction "C_C") (pintype "passive"))
      (node (ref "R14") (pin "2") (pinfunction "2_2") (pintype "passive"))
    )
    (net (code "67") (name "Net-(Q12-PadC)") (class "Default")
      (node (ref "Q12") (pin "C") (pinfunction "C_C") (pintype "passive"))
      (node (ref "R8") (pin "1") (pinfunction "1_1") (pintype "passive"))
    )
    (net (code "68") (name "Net-(Q13-PadC)") (class "Default")
      (node (ref "Q13") (pin "C") (pinfunction "C_C") (pintype "passive"))
      (node (ref "R9") (pin "2") (pinfunction "2_2") (pintype "passive"))
    )
    (net (code "69") (name "Net-(Q14-D)") (class "Default")
      (node (ref "Q14") (pin "3") (pinfunction "D_3") (pintype "passive"))
      (node (ref "R59") (pin "1") (pinfunction "1_1") (pintype "passive"))
      (node (ref "U$4") (pin "4") (pinfunction "G_4") (pintype "passive"))
    )
    (net (code "70") (name "Net-(Q15-D)") (class "Default")
      (node (ref "Q15") (pin "3") (pinfunction "D_3") (pintype "passive"))
      (node (ref "R58") (pin "1") (pinfunction "1_1") (pintype "passive"))
      (node (ref "U$6") (pin "4") (pinfunction "G_4") (pintype "passive"))
    )
    (net (code "71") (name "Net-(Q16-D)") (class "Default")
      (node (ref "Q16") (pin "3") (pinfunction "D_3") (pintype "passive"))
      (node (ref "R57") (pin "1") (pinfunction "1_1") (pintype "passive"))
      (node (ref "U$5") (pin "4") (pinfunction "G_4") (pintype "passive"))
    )
    (net (code "72") (name "Net-(R23-Pad2)") (class "Default")
      (node (ref "R23") (pin "2") (pinfunction "2_2") (pintype "passive"))
      (node (ref "R28") (pin "2") (pinfunction "2_2") (pintype "passive"))
      (node (ref "R29") (pin "1") (pinfunction "1_1") (pintype "passive"))
      (node (ref "R30") (pin "1") (pinfunction "1_1") (pintype "passive"))
    )
    (net (code "73") (name "Net-(R24-Pad1)") (class "Default")
      (node (ref "R24") (pin "1") (pinfunction "1_1") (pintype "passive"))
      (node (ref "R25") (pin "1") (pinfunction "1_1") (pintype "passive"))
      (node (ref "R26") (pin "2") (pinfunction "2_2") (pintype "passive"))
      (node (ref "R27") (pin "2") (pinfunction "2_2") (pintype "passive"))
    )
    (net (code "74") (name "Net-(R49-Pad1)") (class "Default")
      (node (ref "R49") (pin "1") (pinfunction "1_1") (pintype "passive"))
      (node (ref "R50") (pin "1") (pinfunction "1_1") (pintype "passive"))
      (node (ref "R51") (pin "2") (pinfunction "2_2") (pintype "passive"))
      (node (ref "R52") (pin "2") (pinfunction "2_2") (pintype "passive"))
    )
    (net (code "75") (name "Net-(R53-Pad2)") (class "Default")
      (node (ref "R53") (pin "2") (pinfunction "2_2") (pintype "passive"))
      (node (ref "R54") (pin "2") (pinfunction "2_2") (pintype "passive"))
      (node (ref "R55") (pin "1") (pinfunction "1_1") (pintype "passive"))
      (node (ref "R56") (pin "1") (pinfunction "1_1") (pintype "passive"))
    )
    (net (code "76") (name "Net-(X3-P1)") (class "Default")
      (node (ref "U$4") (pin "5") (pinfunction "D_5") (pintype "passive"))
      (node (ref "U$4") (pin "6") (pinfunction "D_6") (pintype "passive"))
      (node (ref "U$4") (pin "7") (pinfunction "D_7") (pintype "passive"))
      (node (ref "U$4") (pin "8") (pinfunction "D_8") (pintype "passive"))
      (node (ref "U$4") (pin "TH") (pinfunction "D_TH") (pintype "passive"))
      (node (ref "X3") (pin "L1") (pinfunction "P1_L1") (pintype "bidirectional"))
    )
    (net (code "77") (name "Net-(X3-P4)") (class "Default")
      (node (ref "R10") (pin "1") (pinfunction "1_1") (pintype "passive"))
      (node (ref "R9") (pin "1") (pinfunction "1_1") (pintype "passive"))
      (node (ref "U$5") (pin "5") (pinfunction "D_5") (pintype "passive"))
      (node (ref "U$5") (pin "6") (pinfunction "D_6") (pintype "passive"))
      (node (ref "U$5") (pin "7") (pinfunction "D_7") (pintype "passive"))
      (node (ref "U$5") (pin "8") (pinfunction "D_8") (pintype "passive"))
      (node (ref "U$5") (pin "TH") (pinfunction "D_TH") (pintype "passive"))
      (node (ref "X3") (pin "L4") (pinfunction "P4_L4") (pintype "bidirectional"))
    )
    (net (code "78") (name "Net-(X6-P1)") (class "Default")
      (node (ref "R4") (pin "1") (pinfunction "1_1") (pintype "passive"))
      (node (ref "R5") (pin "1") (pinfunction "1_1") (pintype "passive"))
      (node (ref "U$2") (pin "5") (pinfunction "D_5") (pintype "passive"))
      (node (ref "U$2") (pin "6") (pinfunction "D_6") (pintype "passive"))
      (node (ref "U$2") (pin "7") (pinfunction "D_7") (pintype "passive"))
      (node (ref "U$2") (pin "8") (pinfunction "D_8") (pintype "passive"))
      (node (ref "U$2") (pin "TH") (pinfunction "D_TH") (pintype "passive"))
      (node (ref "X6") (pin "L1") (pinfunction "P1_L1") (pintype "bidirectional"))
    )
    (net (code "79") (name "Net-(X6-P4)") (class "Default")
      (node (ref "U$1") (pin "5") (pinfunction "D_5") (pintype "passive"))
      (node (ref "U$1") (pin "6") (pinfunction "D_6") (pintype "passive"))
      (node (ref "U$1") (pin "7") (pinfunction "D_7") (pintype "passive"))
      (node (ref "U$1") (pin "8") (pinfunction "D_8") (pintype "passive"))
      (node (ref "U$1") (pin "TH") (pinfunction "D_TH") (pintype "passive"))
      (node (ref "X6") (pin "L4") (pinfunction "P4_L4") (pintype "bidirectional"))
    )
    (net (code "80") (name "unconnected-(IC2-PB0-Pad4)") (class "Default")
      (node (ref "IC2") (pin "4") (pinfunction "PB0_4") (pintype "bidirectional"))
    )
    (net (code "81") (name "unconnected-(IC2-PB1-Pad5)") (class "Default")
      (node (ref "IC2") (pin "5") (pinfunction "PB1_5") (pintype "bidirectional"))
    )
    (net (code "82") (name "unconnected-(IC2-PC0-Pad10)") (class "Default")
      (node (ref "IC2") (pin "10") (pinfunction "PC0_10") (pintype "bidirectional"))
    )
    (net (code "83") (name "unconnected-(IC2-PC6-Pad16)") (class "Default")
      (node (ref "IC2") (pin "16") (pinfunction "PC6_16") (pintype "bidirectional"))
    )
    (net (code "84") (name "unconnected-(IC2-PC7-Pad17)") (class "Default")
      (node (ref "IC2") (pin "17") (pinfunction "PC7_17") (pintype "bidirectional"))
    )
    (net (code "85") (name "unconnected-(IC2-PD4-Pad24)") (class "Default")
      (node (ref "IC2") (pin "24") (pinfunction "PD4_24") (pintype "bidirectional"))
    )
    (net (code "86") (name "unconnected-(IC2-PD5-Pad25)") (class "Default")
      (node (ref "IC2") (pin "25") (pinfunction "PD5_25") (pintype "bidirectional"))
    )
    (net (code "87") (name "unconnected-(IC2-PD6-Pad26)") (class "Default")
      (node (ref "IC2") (pin "26") (pinfunction "PD6_26") (pintype "bidirectional"))
    )
    (net (code "88") (name "unconnected-(IC2-PD7-Pad27)") (class "Default")
      (node (ref "IC2") (pin "27") (pinfunction "PD7_27") (pintype "bidirectional"))
    )
    (net (code "89") (name "unconnected-(IC2-PE1-Pad29)") (class "Default")
      (node (ref "IC2") (pin "29") (pinfunction "PE1_29") (pintype "bidirectional"))
    )
    (net (code "90") (name "unconnected-(IC2-PR0(XT2)-Pad36)") (class "Default")
      (node (ref "IC2") (pin "36") (pinfunction "PR0(XT2)_36") (pintype "bidirectional"))
    )
    (net (code "91") (name "unconnected-(IC2-PR1(XT1)-Pad37)") (class "Default")
      (node (ref "IC2") (pin "37") (pinfunction "PR1(XT1)_37") (pintype "bidirectional"))
    )
    (net (code "92") (name "unconnected-(SV2-3-PadP$3)") (class "Default")
      (node (ref "SV2") (pin "P$3") (pinfunction "3_P$3") (pintype "passive"))
    )
    (net (code "93") (name "unconnected-(SV2-4-PadP$4)") (class "Default")
      (node (ref "SV2") (pin "P$4") (pinfunction "4_P$4") (pintype "passive"))
    )
  )
)
